# HeartbeatDetector.net
KiCad netlist of a schematic drawn in EAGLE
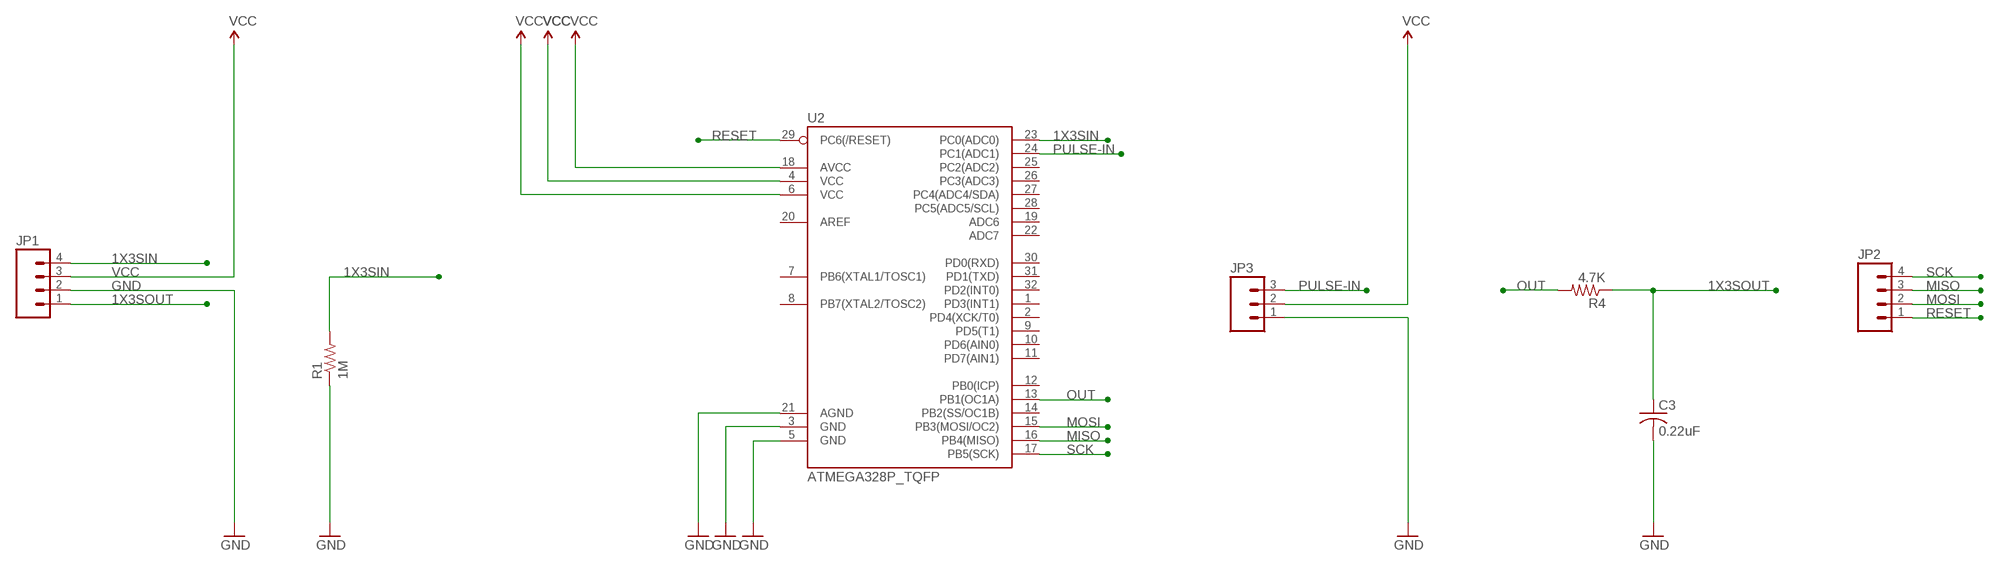
[diagram p0: schematic, sheet 1]

(export (version "E")
  (design (tool "Eeschema 10.0.6"))
  (components
    (comp (ref "C3")
      (value "0.22uF")
      (footprint "eagle-import:C0603")
      (libsource (lib "eagle-import") (part "C-USC0603"))
    )
    (comp (ref "JP1")
      (value "M04PTH")
      (footprint "eagle-import:1X04")
      (libsource (lib "eagle-import") (part "M04PTH"))
    )
    (comp (ref "JP2")
      (value "M04PTH")
      (footprint "eagle-import:1X04")
      (libsource (lib "eagle-import") (part "M04PTH"))
    )
    (comp (ref "JP3")
      (value "M031X03_NO_HOLES")
      (footprint "eagle-import:1X03_NO_HOLES")
      (libsource (lib "eagle-import") (part "M031X03_NO_HOLES"))
    )
    (comp (ref "R1")
      (value "1M")
      (footprint "eagle-import:R0603")
      (libsource (lib "eagle-import") (part "R-US_R0603"))
    )
    (comp (ref "R4")
      (value "4.7K")
      (footprint "eagle-import:R0603")
      (libsource (lib "eagle-import") (part "R-US_R0603"))
    )
    (comp (ref "U2")
      (value "ATMEGA328P_TQFP")
      (footprint "eagle-import:TQFP32-08")
      (libsource (lib "eagle-import") (part "ATMEGA328P_TQFP"))
    )
  )
  (nets
    (net (code "1") (name "/1X3SIN") (class "Default")
      (node (ref "JP1") (pin "4") (pinfunction "4_4") (pintype "passive"))
      (node (ref "R1") (pin "2") (pinfunction "2_2") (pintype "passive"))
      (node (ref "U2") (pin "23") (pinfunction "PC0(ADC0)_23") (pintype "bidirectional"))
    )
    (net (code "2") (name "/1X3SOUT") (class "Default")
      (node (ref "C3") (pin "1") (pinfunction "1_1") (pintype "passive"))
      (node (ref "JP1") (pin "1") (pinfunction "1_1") (pintype "passive"))
      (node (ref "R4") (pin "1") (pinfunction "1_1") (pintype "passive"))
    )
    (net (code "3") (name "/MISO") (class "Default")
      (node (ref "JP2") (pin "3") (pinfunction "3_3") (pintype "passive"))
      (node (ref "U2") (pin "16") (pinfunction "PB4(MISO)_16") (pintype "bidirectional"))
    )
    (net (code "4") (name "/MOSI") (class "Default")
      (node (ref "JP2") (pin "2") (pinfunction "2_2") (pintype "passive"))
      (node (ref "U2") (pin "15") (pinfunction "PB3(MOSI/OC2)_15") (pintype "bidirectional"))
    )
    (net (code "5") (name "/OUT") (class "Default")
      (node (ref "R4") (pin "2") (pinfunction "2_2") (pintype "passive"))
      (node (ref "U2") (pin "13") (pinfunction "PB1(OC1A)_13") (pintype "bidirectional"))
    )
    (net (code "6") (name "/PULSE-IN") (class "Default")
      (node (ref "JP3") (pin "3") (pinfunction "3_3") (pintype "passive"))
      (node (ref "U2") (pin "24") (pinfunction "PC1(ADC1)_24") (pintype "bidirectional"))
    )
    (net (code "7") (name "/RESET") (class "Default")
      (node (ref "JP2") (pin "1") (pinfunction "1_1") (pintype "passive"))
      (node (ref "U2") (pin "29") (pinfunction "PC6(/RESET)_29") (pintype "bidirectional"))
    )
    (net (code "8") (name "/SCK") (class "Default")
      (node (ref "JP2") (pin "4") (pinfunction "4_4") (pintype "passive"))
      (node (ref "U2") (pin "17") (pinfunction "PB5(SCK)_17") (pintype "bidirectional"))
    )
    (net (code "9") (name "GND") (class "Default")
      (node (ref "C3") (pin "2") (pinfunction "2_2") (pintype "passive"))
      (node (ref "JP1") (pin "2") (pinfunction "2_2") (pintype "passive"))
      (node (ref "JP3") (pin "1") (pinfunction "1_1") (pintype "passive"))
      (node (ref "R1") (pin "1") (pinfunction "1_1") (pintype "passive"))
      (node (ref "U2") (pin "21") (pinfunction "AGND_21") (pintype "bidirectional"))
      (node (ref "U2") (pin "3") (pinfunction "GND_3") (pintype "bidirectional"))
      (node (ref "U2") (pin "5") (pinfunction "GND_5") (pintype "bidirectional"))
    )
    (net (code "10") (name "VCC") (class "Default")
      (node (ref "JP1") (pin "3") (pinfunction "3_3") (pintype "passive"))
      (node (ref "JP3") (pin "2") (pinfunction "2_2") (pintype "passive"))
      (node (ref "U2") (pin "18") (pinfunction "AVCC_18") (pintype "bidirectional"))
      (node (ref "U2") (pin "4") (pinfunction "VCC_4") (pintype "bidirectional"))
      (node (ref "U2") (pin "6") (pinfunction "VCC_6") (pintype "bidirectional"))
    )
    (net (code "11") (name "unconnected-(U2-ADC6-Pad19)") (class "Default")
      (node (ref "U2") (pin "19") (pinfunction "ADC6_19") (pintype "bidirectional"))
    )
    (net (code "12") (name "unconnected-(U2-ADC7-Pad22)") (class "Default")
      (node (ref "U2") (pin "22") (pinfunction "ADC7_22") (pintype "bidirectional"))
    )
    (net (code "13") (name "unconnected-(U2-AREF-Pad20)") (class "Default")
      (node (ref "U2") (pin "20") (pinfunction "AREF_20") (pintype "bidirectional"))
    )
    (net (code "14") (name "unconnected-(U2-PB0(ICP)-Pad12)") (class "Default")
      (node (ref "U2") (pin "12") (pinfunction "PB0(ICP)_12") (pintype "bidirectional"))
    )
    (net (code "15") (name "unconnected-(U2-PB2(SS{slash}OC1B)-Pad14)") (class "Default")
      (node (ref "U2") (pin "14") (pinfunction "PB2(SS/OC1B)_14") (pintype "bidirectional"))
    )
    (net (code "16") (name "unconnected-(U2-PB6(XTAL1{slash}TOSC1)-Pad7)") (class "Default")
      (node (ref "U2") (pin "7") (pinfunction "PB6(XTAL1/TOSC1)_7") (pintype "bidirectional"))
    )
    (net (code "17") (name "unconnected-(U2-PB7(XTAL2{slash}TOSC2)-Pad8)") (class "Default")
      (node (ref "U2") (pin "8") (pinfunction "PB7(XTAL2/TOSC2)_8") (pintype "bidirectional"))
    )
    (net (code "18") (name "unconnected-(U2-PC2(ADC2)-Pad25)") (class "Default")
      (node (ref "U2") (pin "25") (pinfunction "PC2(ADC2)_25") (pintype "bidirectional"))
    )
    (net (code "19") (name "unconnected-(U2-PC3(ADC3)-Pad26)") (class "Default")
      (node (ref "U2") (pin "26") (pinfunction "PC3(ADC3)_26") (pintype "bidirectional"))
    )
    (net (code "20") (name "unconnected-(U2-PC4(ADC4{slash}SDA)-Pad27)") (class "Default")
      (node (ref "U2") (pin "27") (pinfunction "PC4(ADC4/SDA)_27") (pintype "bidirectional"))
    )
    (net (code "21") (name "unconnected-(U2-PC5(ADC5{slash}SCL)-Pad28)") (class "Default")
      (node (ref "U2") (pin "28") (pinfunction "PC5(ADC5/SCL)_28") (pintype "bidirectional"))
    )
    (net (code "22") (name "unconnected-(U2-PD0(RXD)-Pad30)") (class "Default")
      (node (ref "U2") (pin "30") (pinfunction "PD0(RXD)_30") (pintype "bidirectional"))
    )
    (net (code "23") (name "unconnected-(U2-PD1(TXD)-Pad31)") (class "Default")
      (node (ref "U2") (pin "31") (pinfunction "PD1(TXD)_31") (pintype "bidirectional"))
    )
    (net (code "24") (name "unconnected-(U2-PD2(INT0)-Pad32)") (class "Default")
      (node (ref "U2") (pin "32") (pinfunction "PD2(INT0)_32") (pintype "bidirectional"))
    )
    (net (code "25") (name "unconnected-(U2-PD3(INT1)-Pad1)") (class "Default")
      (node (ref "U2") (pin "1") (pinfunction "PD3(INT1)_1") (pintype "bidirectional"))
    )
    (net (code "26") (name "unconnected-(U2-PD4(XCK{slash}T0)-Pad2)") (class "Default")
      (node (ref "U2") (pin "2") (pinfunction "PD4(XCK/T0)_2") (pintype "bidirectional"))
    )
    (net (code "27") (name "unconnected-(U2-PD5(T1)-Pad9)") (class "Default")
      (node (ref "U2") (pin "9") (pinfunction "PD5(T1)_9") (pintype "bidirectional"))
    )
    (net (code "28") (name "unconnected-(U2-PD6(AIN0)-Pad10)") (class "Default")
      (node (ref "U2") (pin "10") (pinfunction "PD6(AIN0)_10") (pintype "bidirectional"))
    )
    (net (code "29") (name "unconnected-(U2-PD7(AIN1)-Pad11)") (class "Default")
      (node (ref "U2") (pin "11") (pinfunction "PD7(AIN1)_11") (pintype "bidirectional"))
    )
  )
)
